# o_clone_rev_b.net
KiCad netlist of a schematic drawn in EAGLE
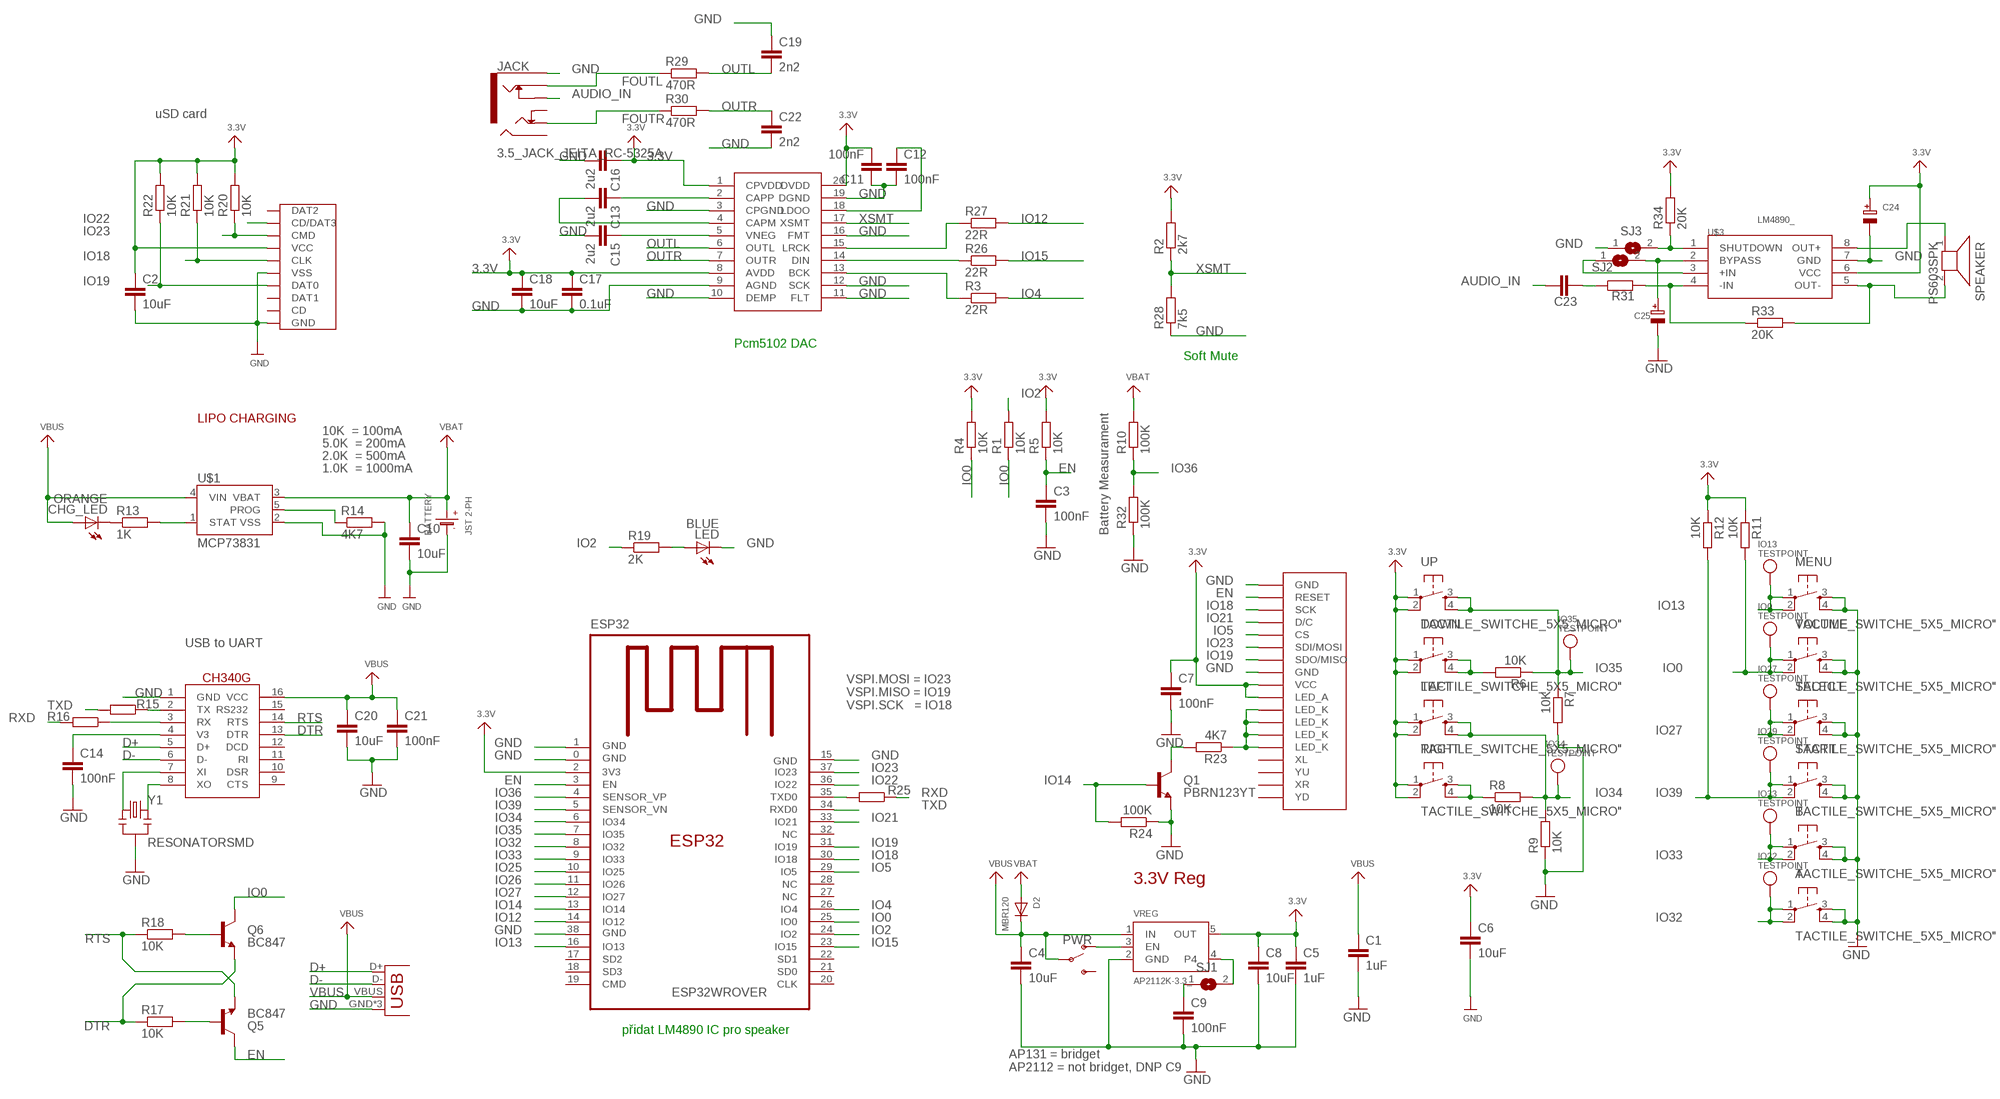
[diagram p0: schematic, sheet 1]

(export (version "E")
  (design (tool "Eeschema 10.0.6"))
  (components
    (comp (ref "A")
      (value "TACTILE_SWITCHE_5X5_MICRO\"")
      (footprint "eagle-import:TACTILE_SWITCH_5X5_MICRO")
      (libsource (lib "eagle-import") (part "TACTILE_SWITCHE_5X5_MICRO{dblquote}"))
    )
    (comp (ref "B")
      (value "TACTILE_SWITCHE_5X5_MICRO\"")
      (footprint "eagle-import:TACTILE_SWITCH_5X5_MICRO")
      (libsource (lib "eagle-import") (part "TACTILE_SWITCHE_5X5_MICRO{dblquote}"))
    )
    (comp (ref "BATTERY")
      (value "JST 2-PH")
      (footprint "eagle-import:JSTPH2")
      (libsource (lib "eagle-import") (part "JST_CONNECTOR"))
    )
    (comp (ref "C1")
      (value "1uF")
      (footprint "eagle-import:C0805")
      (libsource (lib "eagle-import") (part "C-EUC0805"))
    )
    (comp (ref "C2")
      (value "10uF")
      (footprint "eagle-import:C0805")
      (libsource (lib "eagle-import") (part "C-EUC0805"))
    )
    (comp (ref "C3")
      (value "100nF")
      (footprint "eagle-import:C0805")
      (libsource (lib "eagle-import") (part "C-EUC0805"))
    )
    (comp (ref "C4")
      (value "10uF")
      (footprint "eagle-import:C0805")
      (libsource (lib "eagle-import") (part "C-EUC0805"))
    )
    (comp (ref "C5")
      (value "1uF")
      (footprint "eagle-import:C0805")
      (libsource (lib "eagle-import") (part "C-EUC0805"))
    )
    (comp (ref "C6")
      (value "10uF")
      (footprint "eagle-import:C0805")
      (libsource (lib "eagle-import") (part "C-EUC0805"))
    )
    (comp (ref "C7")
      (value "100nF")
      (footprint "eagle-import:C0805")
      (libsource (lib "eagle-import") (part "C-EUC0805"))
    )
    (comp (ref "C8")
      (value "10uF")
      (footprint "eagle-import:C0805")
      (libsource (lib "eagle-import") (part "C-EUC0805"))
    )
    (comp (ref "C9")
      (value "100nF")
      (footprint "eagle-import:C0805")
      (libsource (lib "eagle-import") (part "C-EUC0805"))
    )
    (comp (ref "C10")
      (value "10uF")
      (footprint "eagle-import:C0805")
      (libsource (lib "eagle-import") (part "C-EUC0805"))
    )
    (comp (ref "C11")
      (value "100nF")
      (footprint "eagle-import:C0805")
      (libsource (lib "eagle-import") (part "C-EUC0805"))
    )
    (comp (ref "C12")
      (value "100nF")
      (footprint "eagle-import:C0805")
      (libsource (lib "eagle-import") (part "C-EUC0805"))
    )
    (comp (ref "C13")
      (value "2u2")
      (footprint "eagle-import:C0805")
      (libsource (lib "eagle-import") (part "C-EUC0805"))
    )
    (comp (ref "C14")
      (value "100nF")
      (footprint "eagle-import:C0805")
      (libsource (lib "eagle-import") (part "C-EUC0805"))
    )
    (comp (ref "C15")
      (value "2u2")
      (footprint "eagle-import:C0805")
      (libsource (lib "eagle-import") (part "C-EUC0805"))
    )
    (comp (ref "C16")
      (value "2u2")
      (footprint "eagle-import:C0805")
      (libsource (lib "eagle-import") (part "C-EUC0805"))
    )
    (comp (ref "C17")
      (value "0.1uF")
      (footprint "eagle-import:C0805")
      (libsource (lib "eagle-import") (part "C-EUC0805"))
    )
    (comp (ref "C18")
      (value "10uF")
      (footprint "eagle-import:C0805")
      (libsource (lib "eagle-import") (part "C-EUC0805"))
    )
    (comp (ref "C19")
      (value "2n2")
      (footprint "eagle-import:C0805")
      (libsource (lib "eagle-import") (part "C-EUC0805"))
    )
    (comp (ref "C20")
      (value "10uF")
      (footprint "eagle-import:C0805")
      (libsource (lib "eagle-import") (part "C-EUC0805"))
    )
    (comp (ref "C21")
      (value "100nF")
      (footprint "eagle-import:C0805")
      (libsource (lib "eagle-import") (part "C-EUC0805"))
    )
    (comp (ref "C22")
      (value "2n2")
      (footprint "eagle-import:C0805")
      (libsource (lib "eagle-import") (part "C-EUC0805"))
    )
    (comp (ref "C23")
      (value "0.39uF (Fa:2896582)")
      (footprint "eagle-import:C0805")
      (libsource (lib "eagle-import") (part "C-EUC0805"))
    )
    (comp (ref "C24")
      (value "1uF (Fa:2491436)")
      (footprint "eagle-import:EIA2012")
      (fields (field (name "SPICEPREFIX") "C"))
      (libsource (lib "eagle-import") (part "CAP_TANTALUM_"))
    )
    (comp (ref "C25")
      (value "1uF (Fa:2491436)")
      (footprint "eagle-import:EIA2012")
      (libsource (lib "eagle-import") (part "CAP_TANTALUM_"))
    )
    (comp (ref "CHG_LED")
      (value "ORANGE")
      (footprint "eagle-import:CHIPLED_0805")
      (libsource (lib "eagle-import") (part "LEDCHIPLED_0805"))
    )
    (comp (ref "D2")
      (value "MBR120")
      (footprint "eagle-import:SOD-123")
      (libsource (lib "eagle-import") (part "DIODESOD-123"))
    )
    (comp (ref "DOWN")
      (value "TACTILE_SWITCHE_5X5_MICRO\"")
      (footprint "eagle-import:TACTILE_SWITCH_5X5_MICRO")
      (libsource (lib "eagle-import") (part "TACTILE_SWITCHE_5X5_MICRO{dblquote}"))
    )
    (comp (ref "ESP32")
      (value "ESP32WROVER")
      (footprint "eagle-import:ESP32WROVER")
      (libsource (lib "eagle-import") (part "ESP32WROVER"))
    )
    (comp (ref "IO0")
      (value "TESTPOINT")
      (footprint "eagle-import:TESTPOINT")
      (libsource (lib "eagle-import") (part "TESTPOINT"))
    )
    (comp (ref "IO13")
      (value "TESTPOINT")
      (footprint "eagle-import:TESTPOINT")
      (libsource (lib "eagle-import") (part "TESTPOINT"))
    )
    (comp (ref "IO27")
      (value "TESTPOINT")
      (footprint "eagle-import:TESTPOINT")
      (libsource (lib "eagle-import") (part "TESTPOINT"))
    )
    (comp (ref "IO32")
      (value "TESTPOINT")
      (footprint "eagle-import:TESTPOINT")
      (libsource (lib "eagle-import") (part "TESTPOINT"))
    )
    (comp (ref "IO33")
      (value "TESTPOINT")
      (footprint "eagle-import:TESTPOINT")
      (libsource (lib "eagle-import") (part "TESTPOINT"))
    )
    (comp (ref "IO34")
      (value "TESTPOINT")
      (footprint "eagle-import:TESTPOINT")
      (libsource (lib "eagle-import") (part "TESTPOINT"))
    )
    (comp (ref "IO35")
      (value "TESTPOINT")
      (footprint "eagle-import:TESTPOINT")
      (libsource (lib "eagle-import") (part "TESTPOINT"))
    )
    (comp (ref "IO39")
      (value "TESTPOINT")
      (footprint "eagle-import:TESTPOINT")
      (libsource (lib "eagle-import") (part "TESTPOINT"))
    )
    (comp (ref "JACK")
      (value "3.5_JACK_JEITA_RC-5325A")
      (footprint "eagle-import:3.5_JACK_JEITA_RC-5325A")
      (libsource (lib "eagle-import") (part "3.5_JACK_JEITA_RC-5325A"))
    )
    (comp (ref "LCD")
      (value "ILI9341_3.2LCD_")
      (footprint "eagle-import:LI9341_3.2LCD")
      (libsource (lib "eagle-import") (part "ILI9341_3.2LCD_"))
    )
    (comp (ref "LED")
      (value "BLUE")
      (footprint "eagle-import:CHIPLED_0805")
      (libsource (lib "eagle-import") (part "LEDCHIPLED_0805"))
    )
    (comp (ref "LEFT")
      (value "TACTILE_SWITCHE_5X5_MICRO\"")
      (footprint "eagle-import:TACTILE_SWITCH_5X5_MICRO")
      (libsource (lib "eagle-import") (part "TACTILE_SWITCHE_5X5_MICRO{dblquote}"))
    )
    (comp (ref "MENU")
      (value "TACTILE_SWITCHE_5X5_MICRO\"")
      (footprint "eagle-import:TACTILE_SWITCH_5X5_MICRO")
      (libsource (lib "eagle-import") (part "TACTILE_SWITCHE_5X5_MICRO{dblquote}"))
    )
    (comp (ref "PCM5102")
      (value "PCM5102")
      (footprint "eagle-import:TSSOP20")
      (libsource (lib "eagle-import") (part "PCM5102"))
    )
    (comp (ref "PWR")
      (value "SWITCH-SPDT-SMD-RIGHT-ANGLE")
      (footprint "eagle-import:SWITCH_SPST_SMD_A")
      (libsource (lib "eagle-import") (part "SWITCH-SPDT-SMD-RIGHT-ANGLE"))
    )
    (comp (ref "Q1")
      (value "PBRN123YT")
      (footprint "eagle-import:SOT23-3")
      (libsource (lib "eagle-import") (part "TRANSISTOR_NPNSOT23-3"))
    )
    (comp (ref "Q5")
      (value "BC847")
      (footprint "eagle-import:SOT23-3")
      (libsource (lib "eagle-import") (part "TRANSISTOR_NPNSOT23-3"))
    )
    (comp (ref "Q6")
      (value "BC847")
      (footprint "eagle-import:SOT23-3")
      (libsource (lib "eagle-import") (part "TRANSISTOR_NPNSOT23-3"))
    )
    (comp (ref "R1")
      (value "10K")
      (footprint "eagle-import:R0805")
      (libsource (lib "eagle-import") (part "R-EU_R0805"))
    )
    (comp (ref "R2")
      (value "2k7")
      (footprint "eagle-import:R0805")
      (libsource (lib "eagle-import") (part "R-EU_R0805"))
    )
    (comp (ref "R3")
      (value "22R")
      (footprint "eagle-import:R0805")
      (libsource (lib "eagle-import") (part "R-EU_R0805"))
    )
    (comp (ref "R4")
      (value "10K")
      (footprint "eagle-import:R0805")
      (libsource (lib "eagle-import") (part "R-EU_R0805"))
    )
    (comp (ref "R5")
      (value "10K")
      (footprint "eagle-import:R0805")
      (libsource (lib "eagle-import") (part "R-EU_R0805"))
    )
    (comp (ref "R6")
      (value "10K")
      (footprint "eagle-import:R0805")
      (libsource (lib "eagle-import") (part "R-EU_R0805"))
    )
    (comp (ref "R7")
      (value "10K")
      (footprint "eagle-import:R0805")
      (libsource (lib "eagle-import") (part "R-EU_R0805"))
    )
    (comp (ref "R8")
      (value "10K")
      (footprint "eagle-import:R0805")
      (libsource (lib "eagle-import") (part "R-EU_R0805"))
    )
    (comp (ref "R9")
      (value "10K")
      (footprint "eagle-import:R0805")
      (libsource (lib "eagle-import") (part "R-EU_R0805"))
    )
    (comp (ref "R10")
      (value "100K")
      (footprint "eagle-import:R0805")
      (libsource (lib "eagle-import") (part "R-EU_R0805"))
    )
    (comp (ref "R11")
      (value "10K")
      (footprint "eagle-import:R0805")
      (libsource (lib "eagle-import") (part "R-EU_R0805"))
    )
    (comp (ref "R12")
      (value "10K")
      (footprint "eagle-import:R0805")
      (libsource (lib "eagle-import") (part "R-EU_R0805"))
    )
    (comp (ref "R13")
      (value "1K")
      (footprint "eagle-import:R0805")
      (libsource (lib "eagle-import") (part "R-EU_R0805"))
    )
    (comp (ref "R14")
      (value "4K7")
      (footprint "eagle-import:R0805")
      (libsource (lib "eagle-import") (part "R-EU_R0805"))
    )
    (comp (ref "R15")
      (value "470R")
      (footprint "eagle-import:R0805")
      (libsource (lib "eagle-import") (part "R-EU_R0805"))
    )
    (comp (ref "R16")
      (value "470R")
      (footprint "eagle-import:R0805")
      (libsource (lib "eagle-import") (part "R-EU_R0805"))
    )
    (comp (ref "R17")
      (value "10K")
      (footprint "eagle-import:R0805")
      (libsource (lib "eagle-import") (part "R-EU_R0805"))
    )
    (comp (ref "R18")
      (value "10K")
      (footprint "eagle-import:R0805")
      (libsource (lib "eagle-import") (part "R-EU_R0805"))
    )
    (comp (ref "R19")
      (value "2K")
      (footprint "eagle-import:R0805")
      (libsource (lib "eagle-import") (part "R-EU_R0805"))
    )
    (comp (ref "R20")
      (value "10K")
      (footprint "eagle-import:R0805")
      (libsource (lib "eagle-import") (part "R-EU_R0805"))
    )
    (comp (ref "R21")
      (value "10K")
      (footprint "eagle-import:R0805")
      (libsource (lib "eagle-import") (part "R-EU_R0805"))
    )
    (comp (ref "R22")
      (value "10K")
      (footprint "eagle-import:R0805")
      (libsource (lib "eagle-import") (part "R-EU_R0805"))
    )
    (comp (ref "R23")
      (value "4K7")
      (footprint "eagle-import:R0805")
      (libsource (lib "eagle-import") (part "R-EU_R0805"))
    )
    (comp (ref "R24")
      (value "100K")
      (footprint "eagle-import:R0805")
      (libsource (lib "eagle-import") (part "R-EU_R0805"))
    )
    (comp (ref "R25")
      (value "470R")
      (footprint "eagle-import:R0805")
      (libsource (lib "eagle-import") (part "R-EU_R0805"))
    )
    (comp (ref "R26")
      (value "22R")
      (footprint "eagle-import:R0805")
      (libsource (lib "eagle-import") (part "R-EU_R0805"))
    )
    (comp (ref "R27")
      (value "22R")
      (footprint "eagle-import:R0805")
      (libsource (lib "eagle-import") (part "R-EU_R0805"))
    )
    (comp (ref "R28")
      (value "7k5")
      (footprint "eagle-import:R0805")
      (libsource (lib "eagle-import") (part "R-EU_R0805"))
    )
    (comp (ref "R29")
      (value "470R")
      (footprint "eagle-import:R0805")
      (libsource (lib "eagle-import") (part "R-EU_R0805"))
    )
    (comp (ref "R30")
      (value "470R")
      (footprint "eagle-import:R0805")
      (libsource (lib "eagle-import") (part "R-EU_R0805"))
    )
    (comp (ref "R31")
      (value "20K")
      (footprint "eagle-import:R0805")
      (libsource (lib "eagle-import") (part "R-EU_R0805"))
    )
    (comp (ref "R32")
      (value "100K")
      (footprint "eagle-import:R0805")
      (libsource (lib "eagle-import") (part "R-EU_R0805"))
    )
    (comp (ref "R33")
      (value "20K")
      (footprint "eagle-import:R0805")
      (libsource (lib "eagle-import") (part "R-EU_R0805"))
    )
    (comp (ref "R34")
      (value "20K")
      (footprint "eagle-import:R0805")
      (libsource (lib "eagle-import") (part "R-EU_R0805"))
    )
    (comp (ref "RIGHT")
      (value "TACTILE_SWITCHE_5X5_MICRO\"")
      (footprint "eagle-import:TACTILE_SWITCH_5X5_MICRO")
      (libsource (lib "eagle-import") (part "TACTILE_SWITCHE_5X5_MICRO{dblquote}"))
    )
    (comp (ref "SD_CARD")
      (value "MICRO_SD_CARD\"")
      (footprint "eagle-import:TFP09-2--12B")
      (libsource (lib "eagle-import") (part "MICRO_SD_CARD{dblquote}"))
    )
    (comp (ref "SELECT")
      (value "TACTILE_SWITCHE_5X5_MICRO\"")
      (footprint "eagle-import:TACTILE_SWITCH_5X5_MICRO")
      (libsource (lib "eagle-import") (part "TACTILE_SWITCHE_5X5_MICRO{dblquote}"))
    )
    (comp (ref "SJ1") (value "SJ") (footprint "eagle-import:SJ") (libsource (lib "eagle-import") (part "SJ")))
    (comp (ref "SJ2") (value "SJ") (footprint "eagle-import:SJ") (libsource (lib "eagle-import") (part "SJ")))
    (comp (ref "SJ3") (value "SJ") (footprint "eagle-import:SJ") (libsource (lib "eagle-import") (part "SJ")))
    (comp (ref "SPEAKER")
      (value "PS603SPK")
      (footprint "eagle-import:PS603")
      (libsource (lib "eagle-import") (part "PS603SPK"))
    )
    (comp (ref "START")
      (value "TACTILE_SWITCHE_5X5_MICRO\"")
      (footprint "eagle-import:TACTILE_SWITCH_5X5_MICRO")
      (libsource (lib "eagle-import") (part "TACTILE_SWITCHE_5X5_MICRO{dblquote}"))
    )
    (comp (ref "U$1")
      (value "MCP73831")
      (footprint "eagle-import:SOT95P290X120-5")
      (libsource (lib "eagle-import") (part "MCP73831"))
    )
    (comp (ref "U$3")
      (value "LM4890_")
      (footprint "eagle-import:SOIC127P600X175-8")
      (libsource (lib "eagle-import") (part "LM4890_"))
    )
    (comp (ref "U$23")
      (value "CH340G")
      (footprint "eagle-import:SO16")
      (libsource (lib "eagle-import") (part "CH340G"))
    )
    (comp (ref "UP")
      (value "TACTILE_SWITCHE_5X5_MICRO\"")
      (footprint "eagle-import:TACTILE_SWITCH_5X5_MICRO")
      (libsource (lib "eagle-import") (part "TACTILE_SWITCHE_5X5_MICRO{dblquote}"))
    )
    (comp (ref "USB")
      (value "USB_MICRO_ATTEND_")
      (footprint "eagle-import:USB_MICRO")
      (libsource (lib "eagle-import") (part "USB_MICRO_ATTEND_"))
    )
    (comp (ref "VOLUME")
      (value "TACTILE_SWITCHE_5X5_MICRO\"")
      (footprint "eagle-import:TACTILE_SWITCH_5X5_MICRO")
      (libsource (lib "eagle-import") (part "TACTILE_SWITCHE_5X5_MICRO{dblquote}"))
    )
    (comp (ref "VREG")
      (value "AP2112K-3.3_")
      (footprint "eagle-import:SOT95P290X120-5")
      (libsource (lib "eagle-import") (part "AP2112K-3.3_"))
    )
    (comp (ref "Y1")
      (value "RESONATORSMD")
      (footprint "eagle-import:RESONATOR-SMD")
      (libsource (lib "eagle-import") (part "RESONATORSMD"))
    )
  )
  (nets
    (net (code "1") (name "/AUDIO_IN") (class "Default")
      (node (ref "C23") (pin "1") (pinfunction "1_1") (pintype "passive"))
      (node (ref "JACK") (pin "6") (pinfunction "6_6") (pintype "bidirectional"))
    )
    (net (code "2") (name "/D+") (class "Default")
      (node (ref "U$23") (pin "5") (pinfunction "D+_5") (pintype "bidirectional"))
      (node (ref "USB") (pin "D+") (pinfunction "D+_D+") (pintype "bidirectional"))
    )
    (net (code "3") (name "/D-") (class "Default")
      (node (ref "U$23") (pin "6") (pinfunction "D-_6") (pintype "bidirectional"))
      (node (ref "USB") (pin "D-") (pinfunction "D-_D-") (pintype "bidirectional"))
    )
    (net (code "4") (name "/DTR") (class "Default")
      (node (ref "Q6") (pin "2") (pinfunction "E_2") (pintype "passive"))
      (node (ref "R17") (pin "1") (pinfunction "1_1") (pintype "passive"))
      (node (ref "U$23") (pin "13") (pinfunction "DTR_13") (pintype "bidirectional"))
    )
    (net (code "5") (name "/EN") (class "Default")
      (node (ref "C3") (pin "1") (pinfunction "1_1") (pintype "passive"))
      (node (ref "ESP32") (pin "3") (pinfunction "EN_3") (pintype "bidirectional"))
      (node (ref "LCD") (pin "P$2") (pinfunction "RESET_P$2") (pintype "bidirectional"))
      (node (ref "Q5") (pin "3") (pinfunction "C_3") (pintype "passive"))
      (node (ref "R5") (pin "1") (pinfunction "1_1") (pintype "passive"))
    )
    (net (code "6") (name "/FOUTL") (class "Default")
      (node (ref "JACK") (pin "5") (pinfunction "5_5") (pintype "bidirectional"))
      (node (ref "R29") (pin "1") (pinfunction "1_1") (pintype "passive"))
    )
    (net (code "7") (name "/FOUTR") (class "Default")
      (node (ref "JACK") (pin "3") (pinfunction "3_3") (pintype "bidirectional"))
      (node (ref "R30") (pin "1") (pinfunction "1_1") (pintype "passive"))
    )
    (net (code "8") (name "/IO0") (class "Default")
      (node (ref "ESP32") (pin "25") (pinfunction "IO0_25") (pintype "bidirectional"))
      (node (ref "IO0") (pin "P$1") (pinfunction "P$1_P$1") (pintype "bidirectional"))
      (node (ref "Q6") (pin "3") (pinfunction "C_3") (pintype "passive"))
      (node (ref "R1") (pin "1") (pinfunction "1_1") (pintype "passive"))
      (node (ref "R11") (pin "2") (pinfunction "2_2") (pintype "passive"))
      (node (ref "R4") (pin "1") (pinfunction "1_1") (pintype "passive"))
      (node (ref "VOLUME") (pin "1") (pinfunction "1_1") (pintype "passive"))
      (node (ref "VOLUME") (pin "2") (pinfunction "2_2") (pintype "passive"))
    )
    (net (code "9") (name "/IO2") (class "Default")
      (node (ref "ESP32") (pin "24") (pinfunction "IO2_24") (pintype "bidirectional"))
      (node (ref "R1") (pin "2") (pinfunction "2_2") (pintype "passive"))
      (node (ref "R19") (pin "1") (pinfunction "1_1") (pintype "passive"))
    )
    (net (code "10") (name "/IO4") (class "Default")
      (node (ref "ESP32") (pin "26") (pinfunction "IO4_26") (pintype "bidirectional"))
      (node (ref "R3") (pin "2") (pinfunction "2_2") (pintype "passive"))
    )
    (net (code "11") (name "/IO5") (class "Default")
      (node (ref "ESP32") (pin "29") (pinfunction "IO5_29") (pintype "bidirectional"))
      (node (ref "LCD") (pin "P$5") (pinfunction "CS_P$5") (pintype "bidirectional"))
    )
    (net (code "12") (name "/IO12") (class "Default")
      (node (ref "ESP32") (pin "14") (pinfunction "IO12_14") (pintype "bidirectional"))
      (node (ref "R27") (pin "2") (pinfunction "2_2") (pintype "passive"))
    )
    (net (code "13") (name "/IO13") (class "Default")
      (node (ref "ESP32") (pin "16") (pinfunction "IO13_16") (pintype "bidirectional"))
      (node (ref "IO13") (pin "P$1") (pinfunction "P$1_P$1") (pintype "bidirectional"))
      (node (ref "MENU") (pin "1") (pinfunction "1_1") (pintype "passive"))
      (node (ref "MENU") (pin "2") (pinfunction "2_2") (pintype "passive"))
    )
    (net (code "14") (name "/IO14") (class "Default")
      (node (ref "ESP32") (pin "13") (pinfunction "IO14_13") (pintype "bidirectional"))
      (node (ref "Q1") (pin "1") (pinfunction "B_1") (pintype "passive"))
      (node (ref "R24") (pin "2") (pinfunction "2_2") (pintype "passive"))
    )
    (net (code "15") (name "/IO15") (class "Default")
      (node (ref "ESP32") (pin "23") (pinfunction "IO15_23") (pintype "bidirectional"))
      (node (ref "R26") (pin "2") (pinfunction "2_2") (pintype "passive"))
    )
    (net (code "16") (name "/IO18") (class "Default")
      (node (ref "ESP32") (pin "30") (pinfunction "IO18_30") (pintype "bidirectional"))
      (node (ref "LCD") (pin "P$3") (pinfunction "SCK_P$3") (pintype "bidirectional"))
      (node (ref "R21") (pin "1") (pinfunction "1_1") (pintype "passive"))
      (node (ref "SD_CARD") (pin "CLK") (pinfunction "CLK_CLK") (pintype "bidirectional"))
    )
    (net (code "17") (name "/IO19") (class "Default")
      (node (ref "ESP32") (pin "31") (pinfunction "IO19_31") (pintype "bidirectional"))
      (node (ref "LCD") (pin "P$7") (pinfunction "SDO/MISO_P$7") (pintype "bidirectional"))
      (node (ref "R22") (pin "1") (pinfunction "1_1") (pintype "passive"))
      (node (ref "SD_CARD") (pin "DAT0") (pinfunction "DAT0_DAT0") (pintype "bidirectional"))
    )
    (net (code "18") (name "/IO21") (class "Default")
      (node (ref "ESP32") (pin "33") (pinfunction "IO21_33") (pintype "bidirectional"))
      (node (ref "LCD") (pin "P$4") (pinfunction "D/C_P$4") (pintype "bidirectional"))
    )
    (net (code "19") (name "/IO22") (class "Default")
      (node (ref "ESP32") (pin "36") (pinfunction "IO22_36") (pintype "bidirectional"))
      (node (ref "SD_CARD") (pin "CD/DAT3") (pinfunction "CD/DAT3_CD/DAT3") (pintype "bidirectional"))
    )
    (net (code "20") (name "/IO23") (class "Default")
      (node (ref "ESP32") (pin "37") (pinfunction "IO23_37") (pintype "bidirectional"))
      (node (ref "LCD") (pin "P$6") (pinfunction "SDI/MOSI_P$6") (pintype "bidirectional"))
      (node (ref "R20") (pin "1") (pinfunction "1_1") (pintype "passive"))
      (node (ref "SD_CARD") (pin "CMD") (pinfunction "CMD_CMD") (pintype "bidirectional"))
    )
    (net (code "21") (name "/IO25") (class "Default")
      (node (ref "ESP32") (pin "10") (pinfunction "IO25_10") (pintype "bidirectional"))
    )
    (net (code "22") (name "/IO26") (class "Default")
      (node (ref "ESP32") (pin "11") (pinfunction "IO26_11") (pintype "bidirectional"))
    )
    (net (code "23") (name "/IO27") (class "Default")
      (node (ref "ESP32") (pin "12") (pinfunction "IO27_12") (pintype "bidirectional"))
      (node (ref "IO27") (pin "P$1") (pinfunction "P$1_P$1") (pintype "bidirectional"))
      (node (ref "SELECT") (pin "1") (pinfunction "1_1") (pintype "passive"))
      (node (ref "SELECT") (pin "2") (pinfunction "2_2") (pintype "passive"))
    )
    (net (code "24") (name "/IO32") (class "Default")
      (node (ref "A") (pin "1") (pinfunction "1_1") (pintype "passive"))
      (node (ref "A") (pin "2") (pinfunction "2_2") (pintype "passive"))
      (node (ref "ESP32") (pin "8") (pinfunction "IO32_8") (pintype "bidirectional"))
      (node (ref "IO32") (pin "P$1") (pinfunction "P$1_P$1") (pintype "bidirectional"))
    )
    (net (code "25") (name "/IO33") (class "Default")
      (node (ref "B") (pin "1") (pinfunction "1_1") (pintype "passive"))
      (node (ref "B") (pin "2") (pinfunction "2_2") (pintype "passive"))
      (node (ref "ESP32") (pin "9") (pinfunction "IO33_9") (pintype "bidirectional"))
      (node (ref "IO33") (pin "P$1") (pinfunction "P$1_P$1") (pintype "bidirectional"))
    )
    (net (code "26") (name "/IO34") (class "Default")
      (node (ref "ESP32") (pin "6") (pinfunction "IO34_6") (pintype "bidirectional"))
      (node (ref "IO34") (pin "P$1") (pinfunction "P$1_P$1") (pintype "bidirectional"))
      (node (ref "LEFT") (pin "3") (pinfunction "3_3") (pintype "passive"))
      (node (ref "LEFT") (pin "4") (pinfunction "4_4") (pintype "passive"))
      (node (ref "R8") (pin "2") (pinfunction "2_2") (pintype "passive"))
      (node (ref "R9") (pin "2") (pinfunction "2_2") (pintype "passive"))
    )
    (net (code "27") (name "/IO35") (class "Default")
      (node (ref "ESP32") (pin "7") (pinfunction "IO35_7") (pintype "bidirectional"))
      (node (ref "IO35") (pin "P$1") (pinfunction "P$1_P$1") (pintype "bidirectional"))
      (node (ref "R6") (pin "1") (pinfunction "1_1") (pintype "passive"))
      (node (ref "R7") (pin "1") (pinfunction "1_1") (pintype "passive"))
      (node (ref "UP") (pin "3") (pinfunction "3_3") (pintype "passive"))
      (node (ref "UP") (pin "4") (pinfunction "4_4") (pintype "passive"))
    )
    (net (code "28") (name "/IO36") (class "Default")
      (node (ref "ESP32") (pin "4") (pinfunction "SENSOR_VP_4") (pintype "bidirectional"))
      (node (ref "R10") (pin "1") (pinfunction "1_1") (pintype "passive"))
      (node (ref "R32") (pin "2") (pinfunction "2_2") (pintype "passive"))
    )
    (net (code "29") (name "/IO39") (class "Default")
      (node (ref "ESP32") (pin "5") (pinfunction "SENSOR_VN_5") (pintype "bidirectional"))
      (node (ref "IO39") (pin "P$1") (pinfunction "P$1_P$1") (pintype "bidirectional"))
      (node (ref "R12") (pin "2") (pinfunction "2_2") (pintype "passive"))
      (node (ref "START") (pin "1") (pinfunction "1_1") (pintype "passive"))
      (node (ref "START") (pin "2") (pinfunction "2_2") (pintype "passive"))
    )
    (net (code "30") (name "/OUTL") (class "Default")
      (node (ref "C19") (pin "2") (pinfunction "2_2") (pintype "passive"))
      (node (ref "PCM5102") (pin "6") (pinfunction "OUTL_6") (pintype "bidirectional"))
      (node (ref "R29") (pin "2") (pinfunction "2_2") (pintype "passive"))
    )
    (net (code "31") (name "/OUTR") (class "Default")
      (node (ref "C22") (pin "1") (pinfunction "1_1") (pintype "passive"))
      (node (ref "PCM5102") (pin "7") (pinfunction "OUTR_7") (pintype "bidirectional"))
      (node (ref "R30") (pin "2") (pinfunction "2_2") (pintype "passive"))
    )
    (net (code "32") (name "/RTS") (class "Default")
      (node (ref "Q5") (pin "2") (pinfunction "E_2") (pintype "passive"))
      (node (ref "R18") (pin "1") (pinfunction "1_1") (pintype "passive"))
      (node (ref "U$23") (pin "14") (pinfunction "RTS_14") (pintype "bidirectional"))
    )
    (net (code "33") (name "/RXD") (class "Default")
      (node (ref "R16") (pin "2") (pinfunction "2_2") (pintype "passive"))
      (node (ref "R25") (pin "1") (pinfunction "1_1") (pintype "passive"))
    )
    (net (code "34") (name "/TXD") (class "Default")
      (node (ref "ESP32") (pin "34") (pinfunction "RXD0_34") (pintype "bidirectional"))
      (node (ref "R15") (pin "2") (pinfunction "2_2") (pintype "passive"))
    )
    (net (code "35") (name "/XSMT") (class "Default")
      (node (ref "PCM5102") (pin "17") (pinfunction "XSMT_17") (pintype "bidirectional"))
      (node (ref "R2") (pin "1") (pinfunction "1_1") (pintype "passive"))
      (node (ref "R28") (pin "2") (pinfunction "2_2") (pintype "passive"))
    )
    (net (code "36") (name "3.3V") (class "Default")
      (node (ref "C11") (pin "2") (pinfunction "2_2") (pintype "passive"))
      (node (ref "C16") (pin "1") (pinfunction "1_1") (pintype "passive"))
      (node (ref "C17") (pin "1") (pinfunction "1_1") (pintype "passive"))
      (node (ref "C18") (pin "1") (pinfunction "1_1") (pintype "passive"))
      (node (ref "C2") (pin "1") (pinfunction "1_1") (pintype "passive"))
      (node (ref "C24") (pin "+") (pinfunction "+_+") (pintype "passive"))
      (node (ref "C5") (pin "1") (pinfunction "1_1") (pintype "passive"))
      (node (ref "C6") (pin "1") (pinfunction "1_1") (pintype "passive"))
      (node (ref "C7") (pin "1") (pinfunction "1_1") (pintype "passive"))
      (node (ref "C8") (pin "1") (pinfunction "1_1") (pintype "passive"))
      (node (ref "DOWN") (pin "1") (pinfunction "1_1") (pintype "passive"))
      (node (ref "DOWN") (pin "2") (pinfunction "2_2") (pintype "passive"))
      (node (ref "ESP32") (pin "2") (pinfunction "3V3_2") (pintype "power_in"))
      (node (ref "LCD") (pin "P$10") (pinfunction "LED_A_P$10") (pintype "bidirectional"))
      (node (ref "LCD") (pin "P$9") (pinfunction "VCC_P$9") (pintype "bidirectional"))
      (node (ref "LEFT") (pin "1") (pinfunction "1_1") (pintype "passive"))
      (node (ref "LEFT") (pin "2") (pinfunction "2_2") (pintype "passive"))
      (node (ref "PCM5102") (pin "1") (pinfunction "CPVDD_1") (pintype "bidirectional"))
      (node (ref "PCM5102") (pin "20") (pinfunction "DVDD_20") (pintype "bidirectional"))
      (node (ref "PCM5102") (pin "8") (pinfunction "AVDD_8") (pintype "bidirectional"))
      (node (ref "R11") (pin "1") (pinfunction "1_1") (pintype "passive"))
      (node (ref "R12") (pin "1") (pinfunction "1_1") (pintype "passive"))
      (node (ref "R2") (pin "2") (pinfunction "2_2") (pintype "passive"))
      (node (ref "R20") (pin "2") (pinfunction "2_2") (pintype "passive"))
      (node (ref "R21") (pin "2") (pinfunction "2_2") (pintype "passive"))
      (node (ref "R22") (pin "2") (pinfunction "2_2") (pintype "passive"))
      (node (ref "R34") (pin "2") (pinfunction "2_2") (pintype "passive"))
      (node (ref "R4") (pin "2") (pinfunction "2_2") (pintype "passive"))
      (node (ref "R5") (pin "2") (pinfunction "2_2") (pintype "passive"))
      (node (ref "RIGHT") (pin "1") (pinfunction "1_1") (pintype "passive"))
      (node (ref "RIGHT") (pin "2") (pinfunction "2_2") (pintype "passive"))
      (node (ref "SD_CARD") (pin "VCC") (pinfunction "VCC_VCC") (pintype "bidirectional"))
      (node (ref "U$3") (pin "6") (pinfunction "VCC_6") (pintype "bidirectional"))
      (node (ref "UP") (pin "1") (pinfunction "1_1") (pintype "passive"))
      (node (ref "UP") (pin "2") (pinfunction "2_2") (pintype "passive"))
      (node (ref "VREG") (pin "5") (pinfunction "OUT_5") (pintype "bidirectional"))
    )
    (net (code "37") (name "GND") (class "Default")
      (node (ref "A") (pin "3") (pinfunction "3_3") (pintype "passive"))
      (node (ref "A") (pin "4") (pinfunction "4_4") (pintype "passive"))
      (node (ref "B") (pin "3") (pinfunction "3_3") (pintype "passive"))
      (node (ref "B") (pin "4") (pinfunction "4_4") (pintype "passive"))
      (node (ref "BATTERY") (pin "1") (pinfunction "-_1") (pintype "passive"))
      (node (ref "C1") (pin "2") (pinfunction "2_2") (pintype "passive"))
      (node (ref "C10") (pin "2") (pinfunction "2_2") (pintype "passive"))
      (node (ref "C11") (pin "1") (pinfunction "1_1") (pintype "passive"))
      (node (ref "C12") (pin "2") (pinfunction "2_2") (pintype "passive"))
      (node (ref "C14") (pin "2") (pinfunction "2_2") (pintype "passive"))
      (node (ref "C15") (pin "2") (pinfunction "2_2") (pintype "passive"))
      (node (ref "C16") (pin "2") (pinfunction "2_2") (pintype "passive"))
      (node (ref "C17") (pin "2") (pinfunction "2_2") (pintype "passive"))
      (node (ref "C18") (pin "2") (pinfunction "2_2") (pintype "passive"))
      (node (ref "C19") (pin "1") (pinfunction "1_1") (pintype "passive"))
      (node (ref "C2") (pin "2") (pinfunction "2_2") (pintype "passive"))
      (node (ref "C20") (pin "2") (pinfunction "2_2") (pintype "passive"))
      (node (ref "C21") (pin "2") (pinfunction "2_2") (pintype "passive"))
      (node (ref "C22") (pin "2") (pinfunction "2_2") (pintype "passive"))
      (node (ref "C24") (pin "-") (pinfunction "-_-") (pintype "passive"))
      (node (ref "C25") (pin "-") (pinfunction "-_-") (pintype "passive"))
      (node (ref "C3") (pin "2") (pinfunction "2_2") (pintype "passive"))
      (node (ref "C4") (pin "2") (pinfunction "2_2") (pintype "passive"))
      (node (ref "C5") (pin "2") (pinfunction "2_2") (pintype "passive"))
      (node (ref "C6") (pin "2") (pinfunction "2_2") (pintype "passive"))
      (node (ref "C7") (pin "2") (pinfunction "2_2") (pintype "passive"))
      (node (ref "C8") (pin "2") (pinfunction "2_2") (pintype "passive"))
      (node (ref "C9") (pin "2") (pinfunction "2_2") (pintype "passive"))
      (node (ref "ESP32") (pin "0") (pinfunction "GND_0") (pintype "power_in"))
      (node (ref "ESP32") (pin "1") (pinfunction "GND_1") (pintype "power_in"))
      (node (ref "ESP32") (pin "15") (pinfunction "GND_15") (pintype "power_in"))
      (node (ref "ESP32") (pin "38") (pinfunction "GND_38") (pintype "power_in"))
      (node (ref "JACK") (pin "1") (pinfunction "1_1") (pintype "bidirectional"))
      (node (ref "LCD") (pin "P$1") (pinfunction "GND_P$1") (pintype "bidirectional"))
      (node (ref "LCD") (pin "P$8") (pinfunction "GND_P$8") (pintype "bidirectional"))
      (node (ref "LED") (pin "C") (pinfunction "C_C") (pintype "passive"))
      (node (ref "MENU") (pin "3") (pinfunction "3_3") (pintype "passive"))
      (node (ref "MENU") (pin "4") (pinfunction "4_4") (pintype "passive"))
      (node (ref "PCM5102") (pin "10") (pinfunction "DEMP_10") (pintype "bidirectional"))
      (node (ref "PCM5102") (pin "11") (pinfunction "FLT_11") (pintype "bidirectional"))
      (node (ref "PCM5102") (pin "12") (pinfunction "SCK_12") (pintype "bidirectional"))
      (node (ref "PCM5102") (pin "16") (pinfunction "FMT_16") (pintype "bidirectional"))
      (node (ref "PCM5102") (pin "19") (pinfunction "DGND_19") (pintype "bidirectional"))
      (node (ref "PCM5102") (pin "3") (pinfunction "CPGND_3") (pintype "bidirectional"))
      (node (ref "PCM5102") (pin "9") (pinfunction "AGND_9") (pintype "bidirectional"))
      (node (ref "Q1") (pin "2") (pinfunction "E_2") (pintype "passive"))
      (node (ref "R14") (pin "2") (pinfunction "2_2") (pintype "passive"))
      (node (ref "R24") (pin "1") (pinfunction "1_1") (pintype "passive"))
      (node (ref "R28") (pin "1") (pinfunction "1_1") (pintype "passive"))
      (node (ref "R32") (pin "1") (pinfunction "1_1") (pintype "passive"))
      (node (ref "R7") (pin "2") (pinfunction "2_2") (pintype "passive"))
      (node (ref "R9") (pin "1") (pinfunction "1_1") (pintype "passive"))
      (node (ref "SD_CARD") (pin "GND") (pinfunction "GND_GND") (pintype "bidirectional"))
      (node (ref "SD_CARD") (pin "GND@1") (pinfunction "GND_GND@1") (pintype "bidirectional"))
      (node (ref "SD_CARD") (pin "GND@2") (pinfunction "GND_GND@2") (pintype "bidirectional"))
      (node (ref "SD_CARD") (pin "GND@3") (pinfunction "VSS_GND@3") (pintype "bidirectional"))
      (node (ref "SD_CARD") (pin "VSS") (pinfunction "GND_VSS") (pintype "bidirectional"))
      (node (ref "SELECT") (pin "3") (pinfunction "3_3") (pintype "passive"))
      (node (ref "SELECT") (pin "4") (pinfunction "4_4") (pintype "passive"))
      (node (ref "SJ3") (pin "1") (pinfunction "1_1") (pintype "passive"))
      (node (ref "START") (pin "3") (pinfunction "3_3") (pintype "passive"))
      (node (ref "START") (pin "4") (pinfunction "4_4") (pintype "passive"))
      (node (ref "U$1") (pin "2") (pinfunction "VSS_2") (pintype "power_in"))
      (node (ref "U$23") (pin "1") (pinfunction "GND_1") (pintype "bidirectional"))
      (node (ref "U$3") (pin "7") (pinfunction "GND_7") (pintype "bidirectional"))
      (node (ref "USB") (pin "GND") (pinfunction "GND_GND") (pintype "bidirectional"))
      (node (ref "USB") (pin "GND@2") (pinfunction "GND_GND@2") (pintype "bidirectional"))
      (node (ref "USB") (pin "GND@3") (pinfunction "GND_GND@3") (pintype "bidirectional"))
      (node (ref "VOLUME") (pin "3") (pinfunction "3_3") (pintype "passive"))
      (node (ref "VOLUME") (pin "4") (pinfunction "4_4") (pintype "passive"))
      (node (ref "VREG") (pin "2") (pinfunction "GND_2") (pintype "bidirectional"))
      (node (ref "Y1") (pin "2") (pinfunction "2_2") (pintype "passive"))
    )
    (net (code "38") (name "Net-(C9-Pad1)") (class "Default")
      (node (ref "C9") (pin "1") (pinfunction "1_1") (pintype "passive"))
      (node (ref "SJ1") (pin "1") (pinfunction "1_1") (pintype "passive"))
    )
    (net (code "39") (name "Net-(C23-Pad2)") (class "Default")
      (node (ref "C23") (pin "2") (pinfunction "2_2") (pintype "passive"))
      (node (ref "R31") (pin "1") (pinfunction "1_1") (pintype "passive"))
    )
    (net (code "40") (name "Net-(CHG_LED-PadC)") (class "Default")
      (node (ref "CHG_LED") (pin "C") (pinfunction "C_C") (pintype "passive"))
      (node (ref "R13") (pin "1") (pinfunction "1_1") (pintype "passive"))
    )
    (net (code "41") (name "Net-(DOWN-Pad3)") (class "Default")
      (node (ref "DOWN") (pin "3") (pinfunction "3_3") (pintype "passive"))
      (node (ref "DOWN") (pin "4") (pinfunction "4_4") (pintype "passive"))
      (node (ref "R6") (pin "2") (pinfunction "2_2") (pintype "passive"))
    )
    (net (code "42") (name "Net-(ESP32-TXD0)") (class "Default")
      (node (ref "ESP32") (pin "35") (pinfunction "TXD0_35") (pintype "bidirectional"))
      (node (ref "R25") (pin "2") (pinfunction "2_2") (pintype "passive"))
    )
    (net (code "43") (name "Net-(LCD-LED_K-PadP$11)") (class "Default")
      (node (ref "LCD") (pin "P$11") (pinfunction "LED_K_P$11") (pintype "bidirectional"))
      (node (ref "LCD") (pin "P$12") (pinfunction "LED_K_P$12") (pintype "bidirectional"))
      (node (ref "LCD") (pin "P$13") (pinfunction "LED_K_P$13") (pintype "bidirectional"))
      (node (ref "LCD") (pin "P$14") (pinfunction "LED_K_P$14") (pintype "bidirectional"))
      (node (ref "R23") (pin "1") (pinfunction "1_1") (pintype "passive"))
    )
    (net (code "44") (name "Net-(LED-PadA)") (class "Default")
      (node (ref "LED") (pin "A") (pinfunction "A_A") (pintype "passive"))
      (node (ref "R19") (pin "2") (pinfunction "2_2") (pintype "passive"))
    )
    (net (code "45") (name "Net-(PCM5102-BCK)") (class "Default")
      (node (ref "PCM5102") (pin "13") (pinfunction "BCK_13") (pintype "bidirectional"))
      (node (ref "R3") (pin "1") (pinfunction "1_1") (pintype "passive"))
    )
    (net (code "46") (name "Net-(PCM5102-CAPM)") (class "Default")
      (node (ref "C13") (pin "2") (pinfunction "2_2") (pintype "passive"))
      (node (ref "PCM5102") (pin "4") (pinfunction "CAPM_4") (pintype "bidirectional"))
    )
    (net (code "47") (name "Net-(PCM5102-CAPP)") (class "Default")
      (node (ref "C13") (pin "1") (pinfunction "1_1") (pintype "passive"))
      (node (ref "PCM5102") (pin "2") (pinfunction "CAPP_2") (pintype "bidirectional"))
    )
    (net (code "48") (name "Net-(PCM5102-DIN)") (class "Default")
      (node (ref "PCM5102") (pin "14") (pinfunction "DIN_14") (pintype "bidirectional"))
      (node (ref "R26") (pin "1") (pinfunction "1_1") (pintype "passive"))
    )
    (net (code "49") (name "Net-(PCM5102-LDOO)") (class "Default")
      (node (ref "C12") (pin "1") (pinfunction "1_1") (pintype "passive"))
      (node (ref "PCM5102") (pin "18") (pinfunction "LDOO_18") (pintype "bidirectional"))
    )
    (net (code "50") (name "Net-(PCM5102-LRCK)") (class "Default")
      (node (ref "PCM5102") (pin "15") (pinfunction "LRCK_15") (pintype "bidirectional"))
      (node (ref "R27") (pin "1") (pinfunction "1_1") (pintype "passive"))
    )
    (net (code "51") (name "Net-(PCM5102-VNEG)") (class "Default")
      (node (ref "C15") (pin "1") (pinfunction "1_1") (pintype "passive"))
      (node (ref "PCM5102") (pin "5") (pinfunction "VNEG_5") (pintype "bidirectional"))
    )
    (net (code "52") (name "Net-(PWR-O)") (class "Default")
      (node (ref "PWR") (pin "1") (pinfunction "O_1") (pintype "passive"))
      (node (ref "VREG") (pin "3") (pinfunction "EN_3") (pintype "bidirectional"))
    )
    (net (code "53") (name "Net-(Q1-C)") (class "Default")
      (node (ref "Q1") (pin "3") (pinfunction "C_3") (pintype "passive"))
      (node (ref "R23") (pin "2") (pinfunction "2_2") (pintype "passive"))
    )
    (net (code "54") (name "Net-(Q5-B)") (class "Default")
      (node (ref "Q5") (pin "1") (pinfunction "B_1") (pintype "passive"))
      (node (ref "R17") (pin "2") (pinfunction "2_2") (pintype "passive"))
    )
    (net (code "55") (name "Net-(Q6-B)") (class "Default")
      (node (ref "Q6") (pin "1") (pinfunction "B_1") (pintype "passive"))
      (node (ref "R18") (pin "2") (pinfunction "2_2") (pintype "passive"))
    )
    (net (code "56") (name "Net-(R8-Pad1)") (class "Default")
      (node (ref "R8") (pin "1") (pinfunction "1_1") (pintype "passive"))
      (node (ref "RIGHT") (pin "3") (pinfunction "3_3") (pintype "passive"))
      (node (ref "RIGHT") (pin "4") (pinfunction "4_4") (pintype "passive"))
    )
    (net (code "57") (name "Net-(U$1-PROG)") (class "Default")
      (node (ref "R14") (pin "1") (pinfunction "1_1") (pintype "passive"))
      (node (ref "U$1") (pin "5") (pinfunction "PROG_5") (pintype "input"))
    )
    (net (code "58") (name "Net-(U$1-STAT)") (class "Default")
      (node (ref "R13") (pin "2") (pinfunction "2_2") (pintype "passive"))
      (node (ref "U$1") (pin "1") (pinfunction "STAT_1") (pintype "output"))
    )
    (net (code "59") (name "Net-(U$3-+IN)") (class "Default")
      (node (ref "SJ2") (pin "1") (pinfunction "1_1") (pintype "passive"))
      (node (ref "U$3") (pin "3") (pinfunction "+IN_3") (pintype "bidirectional"))
    )
    (net (code "60") (name "Net-(U$3--IN)") (class "Default")
      (node (ref "R31") (pin "2") (pinfunction "2_2") (pintype "passive"))
      (node (ref "R33") (pin "1") (pinfunction "1_1") (pintype "passive"))
      (node (ref "U$3") (pin "4") (pinfunction "-IN_4") (pintype "bidirectional"))
    )
    (net (code "61") (name "Net-(U$3-BYPASS)") (class "Default")
      (node (ref "C25") (pin "+") (pinfunction "+_+") (pintype "passive"))
      (node (ref "SJ2") (pin "2") (pinfunction "2_2") (pintype "passive"))
      (node (ref "U$3") (pin "2") (pinfunction "BYPASS_2") (pintype "bidirectional"))
    )
    (net (code "62") (name "Net-(U$3-OUT+)") (class "Default")
      (node (ref "SPEAKER") (pin "1") (pinfunction "1_1") (pintype "passive"))
      (node (ref "U$3") (pin "8") (pinfunction "OUT+_8") (pintype "bidirectional"))
    )
    (net (code "63") (name "Net-(U$3-OUT-)") (class "Default")
      (node (ref "R33") (pin "2") (pinfunction "2_2") (pintype "passive"))
      (node (ref "SPEAKER") (pin "2") (pinfunction "2_2") (pintype "passive"))
      (node (ref "U$3") (pin "5") (pinfunction "OUT-_5") (pintype "bidirectional"))
    )
    (net (code "64") (name "Net-(U$3-SHUTDOWN)") (class "Default")
      (node (ref "R34") (pin "1") (pinfunction "1_1") (pintype "passive"))
      (node (ref "SJ3") (pin "2") (pinfunction "2_2") (pintype "passive"))
      (node (ref "U$3") (pin "1") (pinfunction "SHUTDOWN_1") (pintype "bidirectional"))
    )
    (net (code "65") (name "Net-(U$23-RX)") (class "Default")
      (node (ref "R16") (pin "1") (pinfunction "1_1") (pintype "passive"))
      (node (ref "U$23") (pin "3") (pinfunction "RX_3") (pintype "bidirectional"))
    )
    (net (code "66") (name "Net-(U$23-TX)") (class "Default")
      (node (ref "R15") (pin "1") (pinfunction "1_1") (pintype "passive"))
      (node (ref "U$23") (pin "2") (pinfunction "TX_2") (pintype "bidirectional"))
    )
    (net (code "67") (name "Net-(U$23-V3)") (class "Default")
      (node (ref "C14") (pin "1") (pinfunction "1_1") (pintype "passive"))
      (node (ref "U$23") (pin "4") (pinfunction "V3_4") (pintype "bidirectional"))
    )
    (net (code "68") (name "Net-(U$23-XI)") (class "Default")
      (node (ref "U$23") (pin "7") (pinfunction "XI_7") (pintype "bidirectional"))
      (node (ref "Y1") (pin "1") (pinfunction "1_1") (pintype "passive"))
    )
    (net (code "69") (name "Net-(U$23-XO)") (class "Default")
      (node (ref "U$23") (pin "8") (pinfunction "XO_8") (pintype "bidirectional"))
      (node (ref "Y1") (pin "3") (pinfunction "3_3") (pintype "passive"))
    )
    (net (code "70") (name "Net-(VREG-P4)") (class "Default")
      (node (ref "SJ1") (pin "2") (pinfunction "2_2") (pintype "passive"))
      (node (ref "VREG") (pin "4") (pinfunction "P4_4") (pintype "bidirectional"))
    )
    (net (code "71") (name "VBAT") (class "Default")
      (node (ref "BATTERY") (pin "2") (pinfunction "+_2") (pintype "passive"))
      (node (ref "C10") (pin "1") (pinfunction "1_1") (pintype "passive"))
      (node (ref "D2") (pin "A") (pinfunction "A_A") (pintype "passive"))
      (node (ref "R10") (pin "2") (pinfunction "2_2") (pintype "passive"))
      (node (ref "U$1") (pin "3") (pinfunction "VBAT_3") (pintype "power_in"))
    )
    (net (code "72") (name "VBUS") (class "Default")
      (node (ref "C1") (pin "1") (pinfunction "1_1") (pintype "passive"))
      (node (ref "C20") (pin "1") (pinfunction "1_1") (pintype "passive"))
      (node (ref "C21") (pin "1") (pinfunction "1_1") (pintype "passive"))
      (node (ref "C4") (pin "1") (pinfunction "1_1") (pintype "passive"))
      (node (ref "CHG_LED") (pin "A") (pinfunction "A_A") (pintype "passive"))
      (node (ref "D2") (pin "C") (pinfunction "C_C") (pintype "passive"))
      (node (ref "PWR") (pin "2") (pinfunction "P_2") (pintype "passive"))
      (node (ref "U$1") (pin "4") (pinfunction "VIN_4") (pintype "power_in"))
      (node (ref "U$23") (pin "16") (pinfunction "VCC_16") (pintype "bidirectional"))
      (node (ref "USB") (pin "VBUS") (pinfunction "VBUS_VBUS") (pintype "bidirectional"))
      (node (ref "VREG") (pin "1") (pinfunction "IN_1") (pintype "bidirectional"))
    )
    (net (code "73") (name "unconnected-(ESP32-CLK-Pad20)") (class "Default")
      (node (ref "ESP32") (pin "20") (pinfunction "CLK_20") (pintype "bidirectional"))
    )
    (net (code "74") (name "unconnected-(ESP32-CMD-Pad19)") (class "Default")
      (node (ref "ESP32") (pin "19") (pinfunction "CMD_19") (pintype "bidirectional"))
    )
    (net (code "75") (name "unconnected-(ESP32-NC-Pad27)") (class "Default")
      (node (ref "ESP32") (pin "27") (pinfunction "NC_27") (pintype "bidirectional"))
    )
    (net (code "76") (name "unconnected-(ESP32-NC-Pad28)") (class "Default")
      (node (ref "ESP32") (pin "28") (pinfunction "NC_28") (pintype "bidirectional"))
    )
    (net (code "77") (name "unconnected-(ESP32-NC-Pad32)") (class "Default")
      (node (ref "ESP32") (pin "32") (pinfunction "NC_32") (pintype "bidirectional"))
    )
    (net (code "78") (name "unconnected-(ESP32-SD0-Pad21)") (class "Default")
      (node (ref "ESP32") (pin "21") (pinfunction "SD0_21") (pintype "bidirectional"))
    )
    (net (code "79") (name "unconnected-(ESP32-SD1-Pad22)") (class "Default")
      (node (ref "ESP32") (pin "22") (pinfunction "SD1_22") (pintype "bidirectional"))
    )
    (net (code "80") (name "unconnected-(ESP32-SD2-Pad17)") (class "Default")
      (node (ref "ESP32") (pin "17") (pinfunction "SD2_17") (pintype "bidirectional"))
    )
    (net (code "81") (name "unconnected-(ESP32-SD3-Pad18)") (class "Default")
      (node (ref "ESP32") (pin "18") (pinfunction "SD3_18") (pintype "bidirectional"))
    )
    (net (code "82") (name "unconnected-(JACK-Pad2)") (class "Default")
      (node (ref "JACK") (pin "2") (pinfunction "2_2") (pintype "bidirectional"))
    )
    (net (code "83") (name "unconnected-(JACK-Pad4)") (class "Default")
      (node (ref "JACK") (pin "4") (pinfunction "4_4") (pintype "bidirectional"))
    )
    (net (code "84") (name "unconnected-(LCD-XL-PadP$15)") (class "Default")
      (node (ref "LCD") (pin "P$15") (pinfunction "XL_P$15") (pintype "bidirectional"))
    )
    (net (code "85") (name "unconnected-(LCD-XR-PadP$16)") (class "Default")
      (node (ref "LCD") (pin "P$16") (pinfunction "XR_P$16") (pintype "bidirectional"))
    )
    (net (code "86") (name "unconnected-(LCD-YD-PadP$17)") (class "Default")
      (node (ref "LCD") (pin "P$17") (pinfunction "YD_P$17") (pintype "bidirectional"))
    )
    (net (code "87") (name "unconnected-(LCD-YU-PadP$18)") (class "Default")
      (node (ref "LCD") (pin "P$18") (pinfunction "YU_P$18") (pintype "bidirectional"))
    )
    (net (code "88") (name "unconnected-(PWR-S-Pad3)") (class "Default")
      (node (ref "PWR") (pin "3") (pinfunction "S_3") (pintype "passive"))
    )
    (net (code "89") (name "unconnected-(SD_CARD-PadCD)") (class "Default")
      (node (ref "SD_CARD") (pin "CD") (pinfunction "CD_CD") (pintype "bidirectional"))
    )
    (net (code "90") (name "unconnected-(SD_CARD-PadDAT1)") (class "Default")
      (node (ref "SD_CARD") (pin "DAT1") (pinfunction "DAT1_DAT1") (pintype "bidirectional"))
    )
    (net (code "91") (name "unconnected-(SD_CARD-PadDAT2)") (class "Default")
      (node (ref "SD_CARD") (pin "DAT2") (pinfunction "DAT2_DAT2") (pintype "bidirectional"))
    )
    (net (code "92") (name "unconnected-(U$23-CTS-Pad9)") (class "Default")
      (node (ref "U$23") (pin "9") (pinfunction "CTS_9") (pintype "bidirectional"))
    )
    (net (code "93") (name "unconnected-(U$23-DCD-Pad12)") (class "Default")
      (node (ref "U$23") (pin "12") (pinfunction "DCD_12") (pintype "bidirectional"))
    )
    (net (code "94") (name "unconnected-(U$23-DSR-Pad10)") (class "Default")
      (node (ref "U$23") (pin "10") (pinfunction "DSR_10") (pintype "bidirectional"))
    )
    (net (code "95") (name "unconnected-(U$23-RI-Pad11)") (class "Default")
      (node (ref "U$23") (pin "11") (pinfunction "RI_11") (pintype "bidirectional"))
    )
    (net (code "96") (name "unconnected-(U$23-RS232-Pad15)") (class "Default")
      (node (ref "U$23") (pin "15") (pinfunction "RS232_15") (pintype "bidirectional"))
    )
  )
)
